# 07_DIGITAL_TRANSLATION.net
KiCad netlist of a schematic drawn in Altium Designer
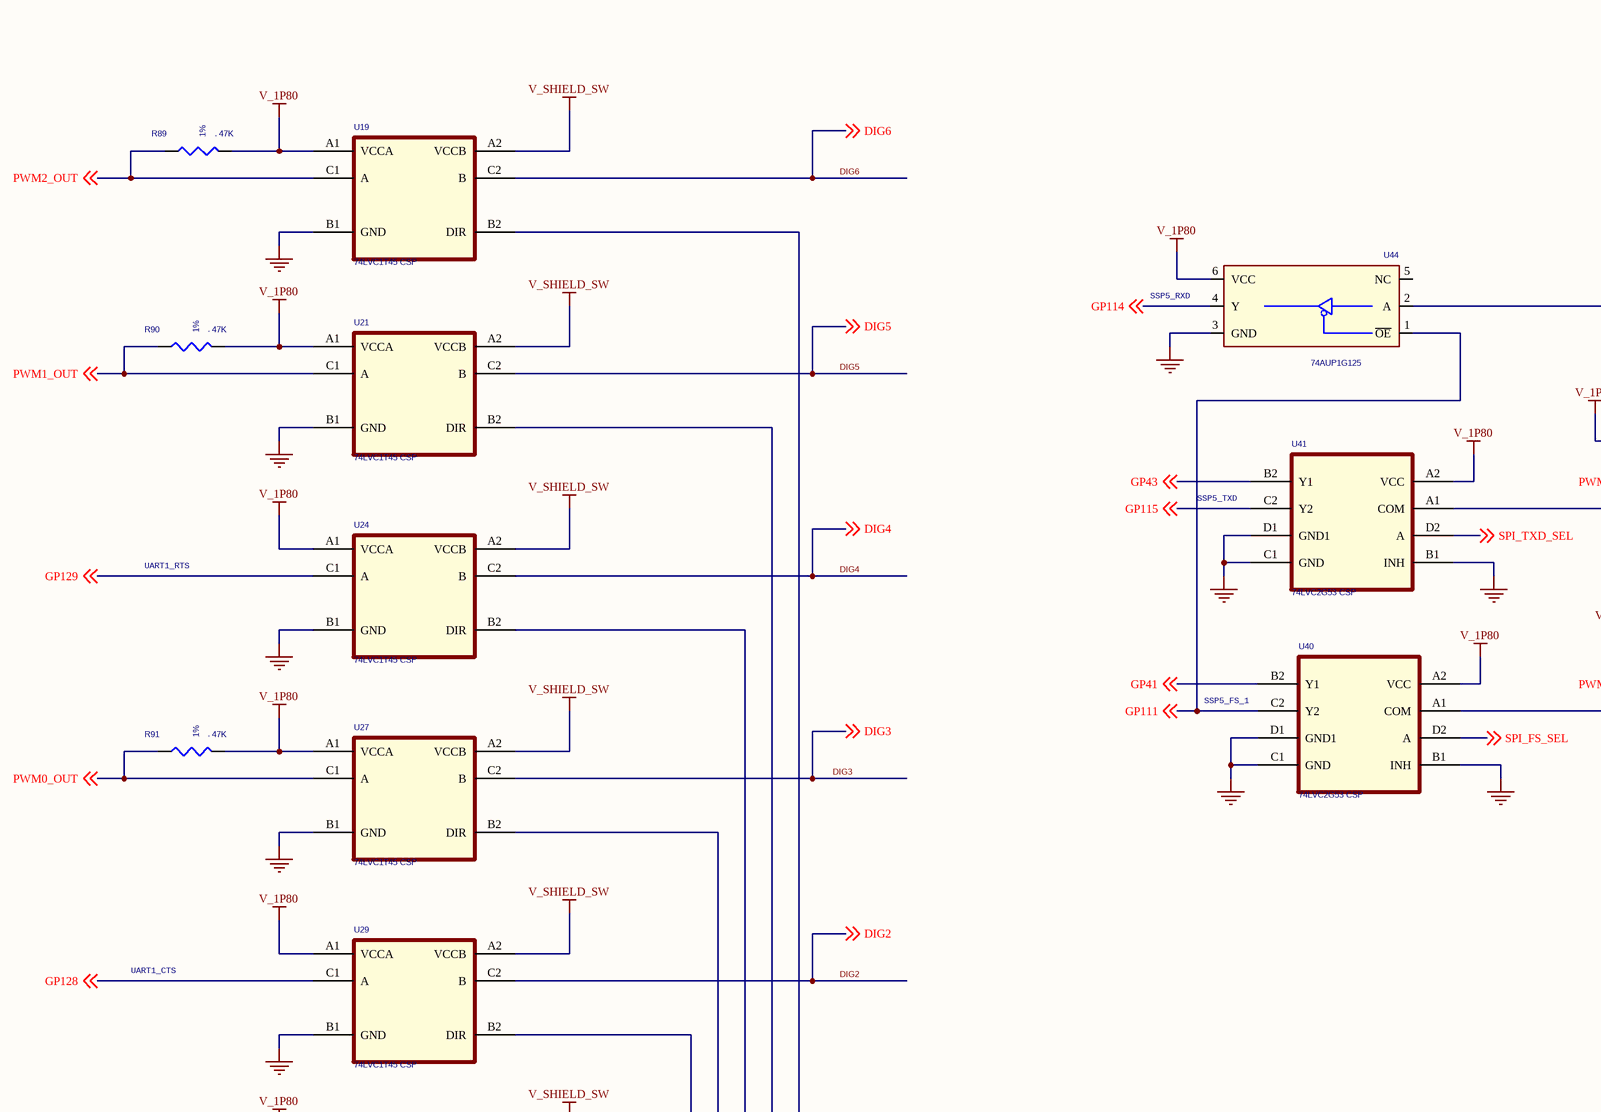
[diagram p0: 07) DIGITAL TRANSLATION.SchDoc, top left]
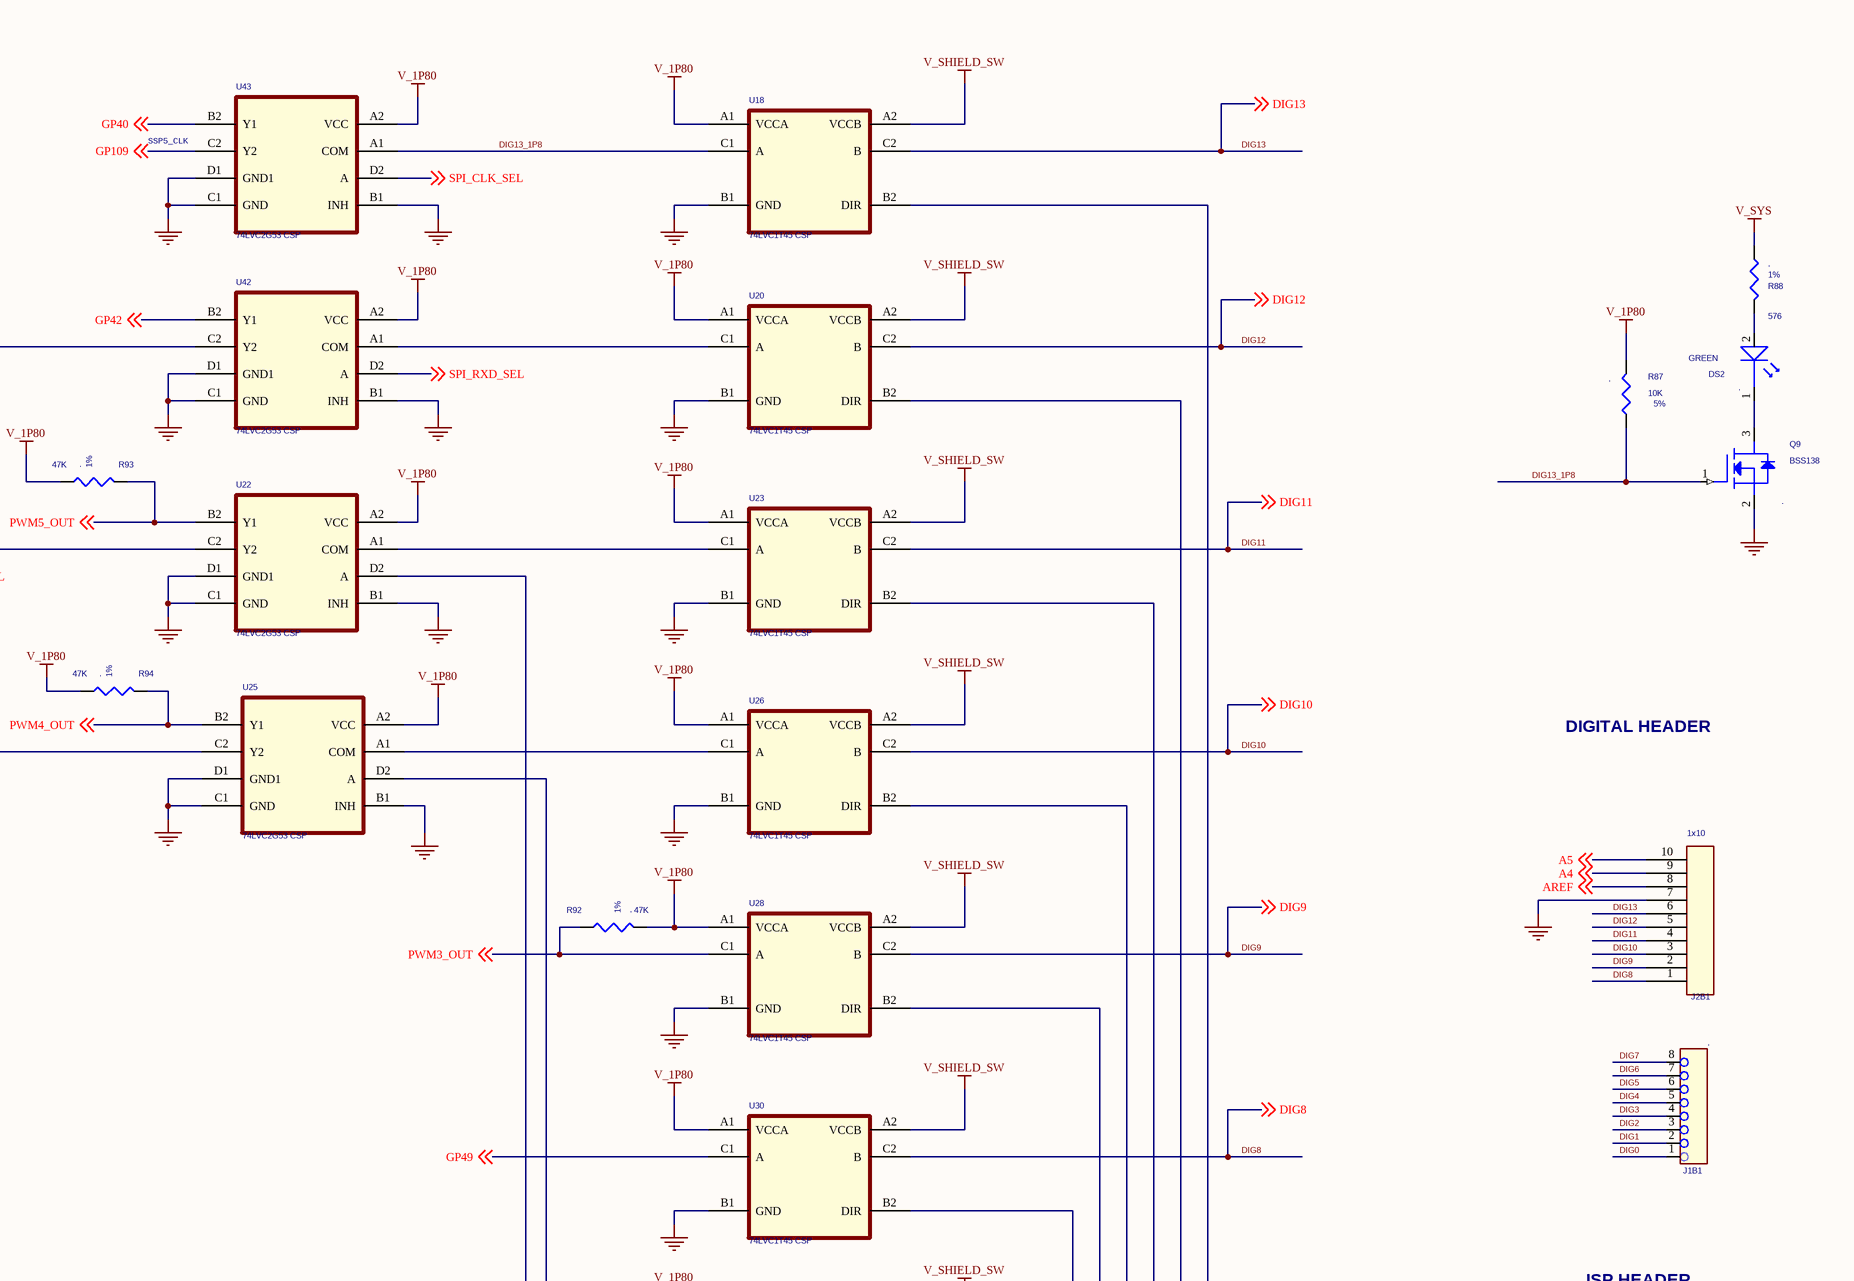
[diagram p1: 07) DIGITAL TRANSLATION.SchDoc, top right]
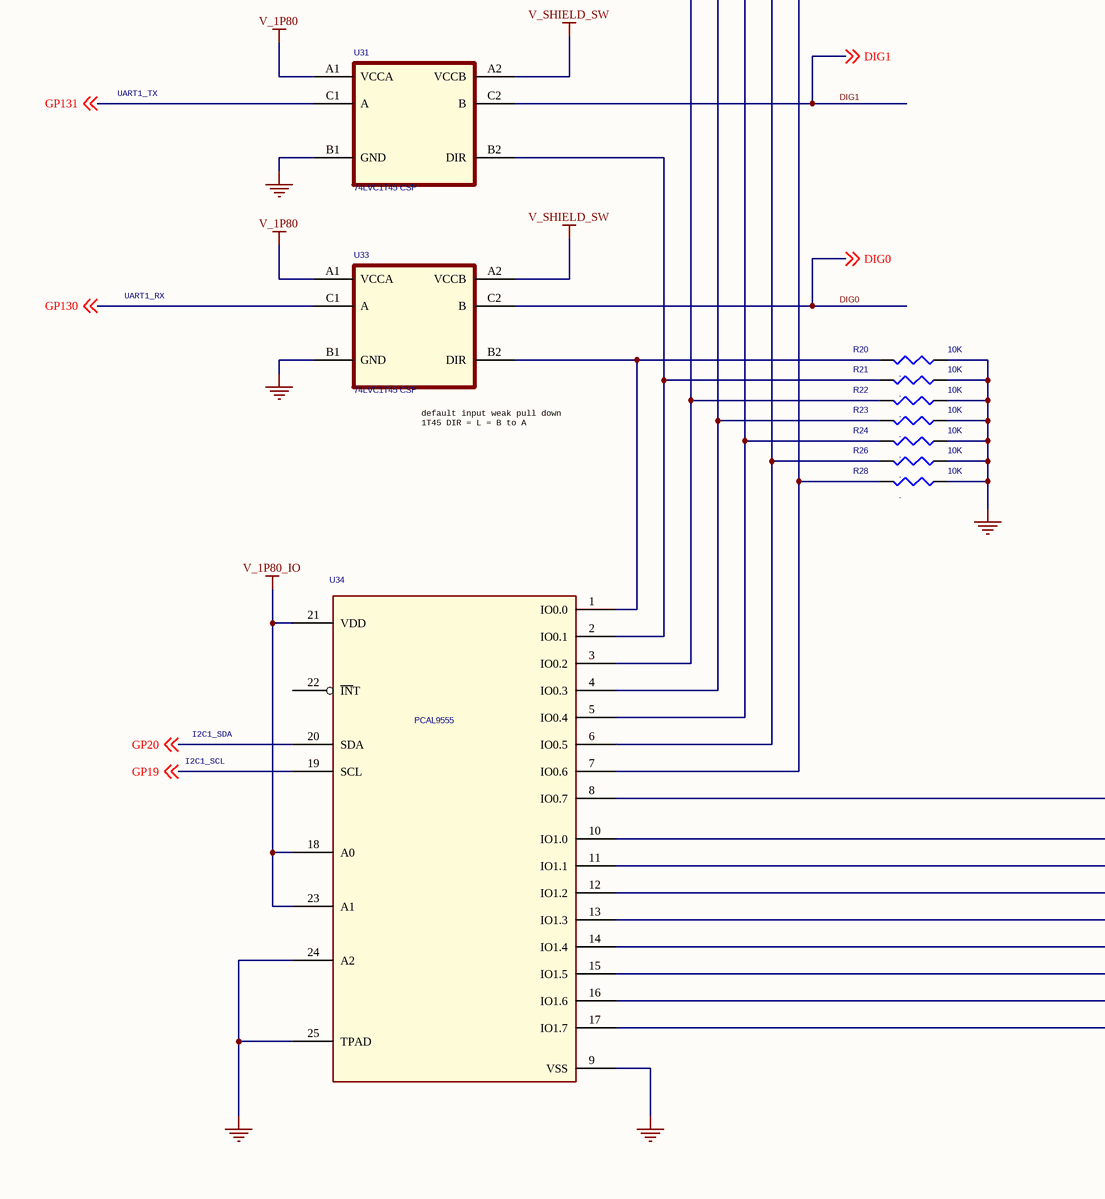
[diagram p2: 07) DIGITAL TRANSLATION.SchDoc, bottom left]
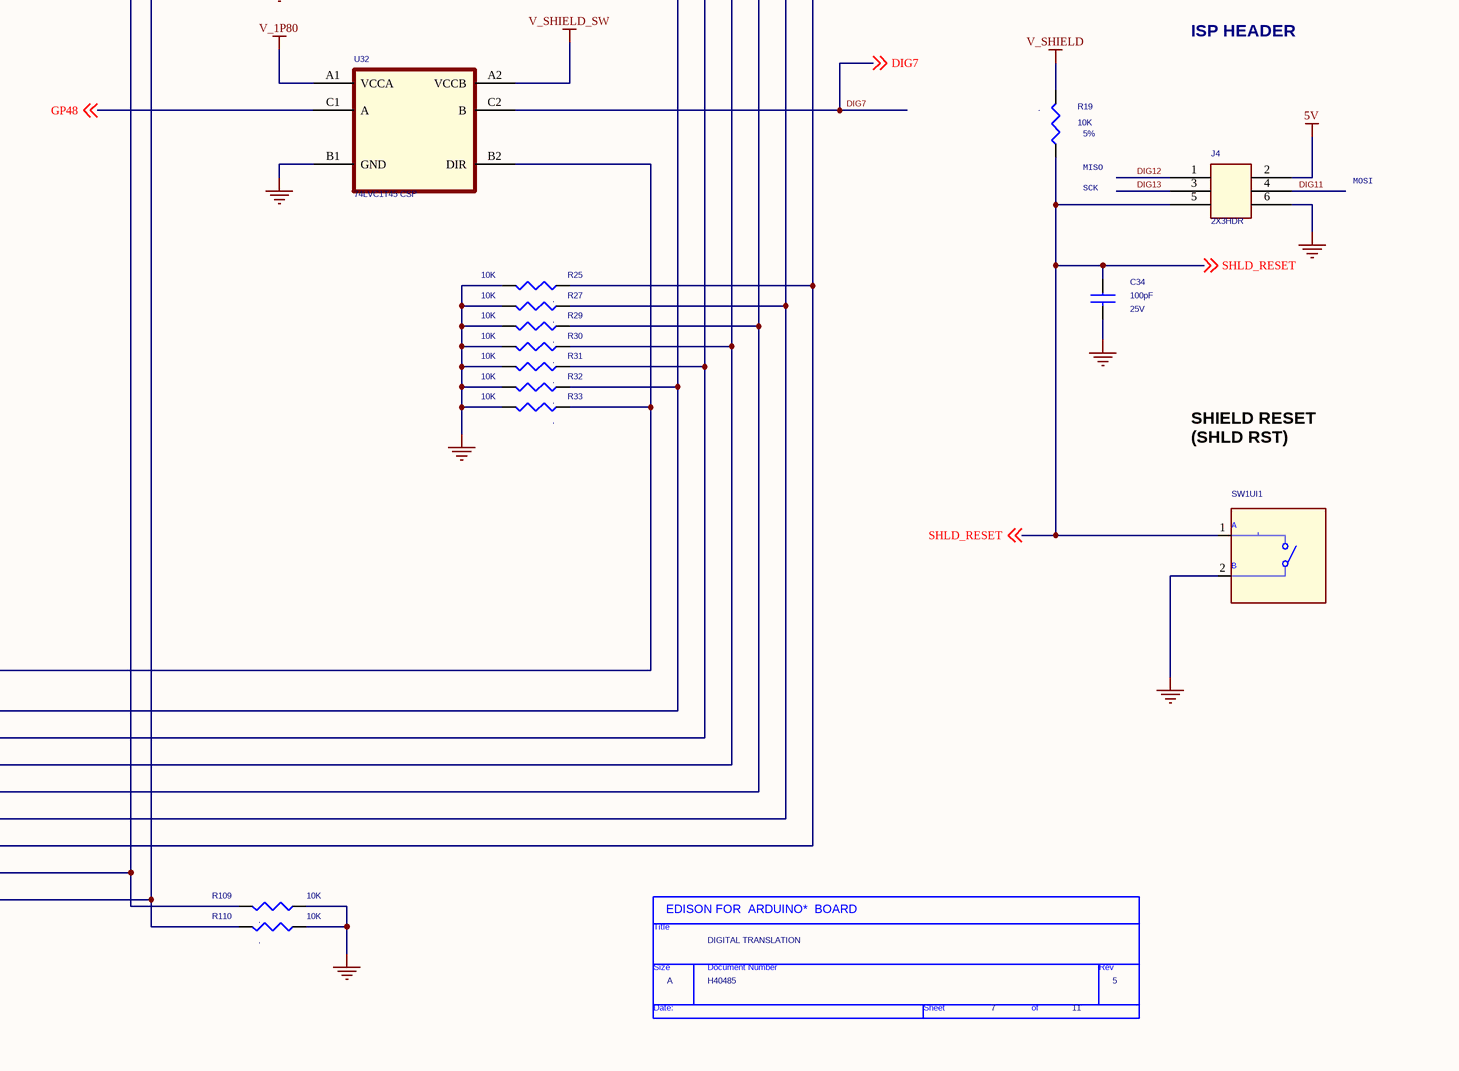
[diagram p3: 07) DIGITAL TRANSLATION.SchDoc, bottom right]

(export (version "E")
  (design (tool "Eeschema 10.0.6"))
  (components
    (comp (ref "C34")
      (value "100pF")
      (footprint "SMC0201")
      (description "CAPC,C0G,0201,100.000PF,25.000V,+/- 5%")
      (fields (field (name "PART_NUMBER") "D70542-001") (field (name "RATING") "25V"))
      (libsource (lib "*") (part "CAPC,COG,0201,25V,5%,100pF"))
    )
    (comp (ref "DS2")
      (value "GREEN")
      (footprint "smled0402")
      (description "LED,1005,SM,GRN,V,1.00,RC,1")
      (fields (field (name "NO_STUFF") ".") (field (name "PART_NUMBER") "E54986-003"))
      (libsource (lib "*") (part "LED,SMT,GREEN,V,0402"))
    )
    (comp (ref "J1B1")
      (value "CON8_HDR")
      (footprint "1x8hdr_p100in_th")
      (description "CONN,PLUG,VERT,1X8,2.54MM,THM,90147_1108")
      (fields (field (name "NO_STUFF") ".") (field (name "PART_NUMBER") "H46118-001"))
      (libsource (lib "*") (part "CON8,HDR,TH,0.1in,E70026-001"))
    )
    (comp (ref "J2B1")
      (value "1x10")
      (footprint "con10_1x10")
      (description "CONN,PLUG,VERT,1X10,2.54MM,THM,10CIRCUITS,90147_1110")
      (fields (field (name "PART_NUMBER") "H46116-001"))
      (libsource (lib "*") (part "CON10,1X10,0.1,0.093,E74918-001"))
    )
    (comp (ref "J4")
      (value "2X3HDR")
      (footprint "HDR_2X3DP")
      (description "CONN,HDR,2X3,PLG,VT,0.1,0.93 ST")
      (fields (field (name "PART_NUMBER") "H18587-001"))
      (libsource (lib "*") (part "CON6,HDR,TH,0_0.1,C77978-007"))
    )
    (comp (ref "Q9")
      (value "BSS138")
      (footprint "SOT23")
      (description "IC,DS,FET N,SOT-23,BSS138LT3G")
      (fields (field (name "NO_STUFF") ".") (field (name "PART_NUMBER") "C81974-001"))
      (libsource (lib "*") (part "XSTR,BSS138,FET,NCH,SOT23"))
    )
    (comp (ref "R19")
      (value "10K")
      (footprint "SMR0201")
      (description "RES D,0201,10.00 kOHM,5.00%,1/20W,YES")
      (fields
        (field (name "NO_STUFF") ".")
        (field (name "TOL") "5%")
        (field (name "PART_NUMBER") "C80792-002")
      )
      (libsource (lib "*") (part "RESD,0201,5%,1/20W,10K"))
    )
    (comp (ref "R20")
      (value "10K")
      (footprint "SMR0201")
      (description "RES D,0201,10.00 kOHM,5.00%,1/20W,YES")
      (fields (field (name "NO_STUFF") ".") (field (name "PART_NUMBER") "C80792-002"))
      (libsource (lib "*") (part "RESD,0201,5%,1/20W,10K"))
    )
    (comp (ref "R21")
      (value "10K")
      (footprint "SMR0201")
      (description "RES D,0201,10.00 kOHM,5.00%,1/20W,YES")
      (fields (field (name "NO_STUFF") ".") (field (name "PART_NUMBER") "C80792-002"))
      (libsource (lib "*") (part "RESD,0201,5%,1/20W,10K"))
    )
    (comp (ref "R22")
      (value "10K")
      (footprint "SMR0201")
      (description "RES D,0201,10.00 kOHM,5.00%,1/20W,YES")
      (fields (field (name "NO_STUFF") ".") (field (name "PART_NUMBER") "C80792-002"))
      (libsource (lib "*") (part "RESD,0201,5%,1/20W,10K"))
    )
    (comp (ref "R23")
      (value "10K")
      (footprint "SMR0201")
      (description "RES D,0201,10.00 kOHM,5.00%,1/20W,YES")
      (fields (field (name "NO_STUFF") ".") (field (name "PART_NUMBER") "C80792-002"))
      (libsource (lib "*") (part "RESD,0201,5%,1/20W,10K"))
    )
    (comp (ref "R24")
      (value "10K")
      (footprint "SMR0201")
      (description "RES D,0201,10.00 kOHM,5.00%,1/20W,YES")
      (fields (field (name "NO_STUFF") ".") (field (name "PART_NUMBER") "C80792-002"))
      (libsource (lib "*") (part "RESD,0201,5%,1/20W,10K"))
    )
    (comp (ref "R25")
      (value "10K")
      (footprint "SMR0201")
      (description "RES D,0201,10.00 kOHM,5.00%,1/20W,YES")
      (fields (field (name "NO_STUFF") ".") (field (name "PART_NUMBER") "C80792-002"))
      (libsource (lib "*") (part "RESD,0201,5%,1/20W,10K"))
    )
    (comp (ref "R26")
      (value "10K")
      (footprint "SMR0201")
      (description "RES D,0201,10.00 kOHM,5.00%,1/20W,YES")
      (fields (field (name "NO_STUFF") ".") (field (name "PART_NUMBER") "C80792-002"))
      (libsource (lib "*") (part "RESD,0201,5%,1/20W,10K"))
    )
    (comp (ref "R27")
      (value "10K")
      (footprint "SMR0201")
      (description "RES D,0201,10.00 kOHM,5.00%,1/20W,YES")
      (fields (field (name "NO_STUFF") ".") (field (name "PART_NUMBER") "C80792-002"))
      (libsource (lib "*") (part "RESD,0201,5%,1/20W,10K"))
    )
    (comp (ref "R28")
      (value "10K")
      (footprint "SMR0201")
      (description "RES D,0201,10.00 kOHM,5.00%,1/20W,YES")
      (fields (field (name "NO_STUFF") ".") (field (name "PART_NUMBER") "C80792-002"))
      (libsource (lib "*") (part "RESD,0201,5%,1/20W,10K"))
    )
    (comp (ref "R29")
      (value "10K")
      (footprint "SMR0201")
      (description "RES D,0201,10.00 kOHM,5.00%,1/20W,YES")
      (fields (field (name "NO_STUFF") ".") (field (name "PART_NUMBER") "C80792-002"))
      (libsource (lib "*") (part "RESD,0201,5%,1/20W,10K"))
    )
    (comp (ref "R30")
      (value "10K")
      (footprint "SMR0201")
      (description "RES D,0201,10.00 kOHM,5.00%,1/20W,YES")
      (fields (field (name "NO_STUFF") ".") (field (name "PART_NUMBER") "C80792-002"))
      (libsource (lib "*") (part "RESD,0201,5%,1/20W,10K"))
    )
    (comp (ref "R31")
      (value "10K")
      (footprint "SMR0201")
      (description "RES D,0201,10.00 kOHM,5.00%,1/20W,YES")
      (fields (field (name "NO_STUFF") ".") (field (name "PART_NUMBER") "C80792-002"))
      (libsource (lib "*") (part "RESD,0201,5%,1/20W,10K"))
    )
    (comp (ref "R32")
      (value "10K")
      (footprint "SMR0201")
      (description "RES D,0201,10.00 kOHM,5.00%,1/20W,YES")
      (fields (field (name "NO_STUFF") ".") (field (name "PART_NUMBER") "C80792-002"))
      (libsource (lib "*") (part "RESD,0201,5%,1/20W,10K"))
    )
    (comp (ref "R33")
      (value "10K")
      (footprint "SMR0201")
      (description "RES D,0201,10.00 kOHM,5.00%,1/20W,YES")
      (fields (field (name "NO_STUFF") ".") (field (name "PART_NUMBER") "C80792-002"))
      (libsource (lib "*") (part "RESD,0201,5%,1/20W,10K"))
    )
    (comp (ref "R87")
      (value "10K")
      (footprint "SMR0201")
      (description "RES D,0201,10.00 kOHM,5.00%,1/20W,YES")
      (fields
        (field (name "NO_STUFF") ".")
        (field (name "TOL") "5%")
        (field (name "PART_NUMBER") "C80792-002")
      )
      (libsource (lib "*") (part "RESD,0201,5%,1/20W,10K"))
    )
    (comp (ref "R88")
      (value "576")
      (footprint "SMR0201")
      (description "RES D,0402,576.00 OHM,1.00%,1/16W,YES")
      (fields
        (field (name "NO_STUFF") ".")
        (field (name "TOL") "1%")
        (field (name "PART_NUMBER") "A93548-403")
      )
      (libsource (lib "*") (part "RESD,0201,1%,1/20W,562"))
    )
    (comp (ref "R89")
      (value "47K")
      (footprint "SMR0201")
      (description "RES_D,0201,47.0kOHM,1.00%,1/20W,")
      (fields
        (field (name "PART_NUMBER") "C48657-118")
        (field (name "TOL") "1%")
        (field (name "NO_STUFF") ".")
      )
      (libsource (lib "*") (part "RESD,0201,1%,1/20W,47K"))
    )
    (comp (ref "R90")
      (value "47K")
      (footprint "SMR0201")
      (description "RES_D,0201,47.0kOHM,1.00%,1/20W,")
      (fields
        (field (name "PART_NUMBER") "C48657-118")
        (field (name "TOL") "1%")
        (field (name "NO_STUFF") ".")
      )
      (libsource (lib "*") (part "RESD,0201,1%,1/20W,47K"))
    )
    (comp (ref "R91")
      (value "47K")
      (footprint "SMR0201")
      (description "RES_D,0201,47.0kOHM,1.00%,1/20W,")
      (fields
        (field (name "PART_NUMBER") "C48657-118")
        (field (name "TOL") "1%")
        (field (name "NO_STUFF") ".")
      )
      (libsource (lib "*") (part "RESD,0201,1%,1/20W,47K"))
    )
    (comp (ref "R92")
      (value "47K")
      (footprint "SMR0201")
      (description "RES_D,0201,47.0kOHM,1.00%,1/20W,")
      (fields
        (field (name "PART_NUMBER") "C48657-118")
        (field (name "TOL") "1%")
        (field (name "NO_STUFF") ".")
      )
      (libsource (lib "*") (part "RESD,0201,1%,1/20W,47K"))
    )
    (comp (ref "R93")
      (value "47K")
      (footprint "SMR0201")
      (description "RES_D,0201,47.0kOHM,1.00%,1/20W,")
      (fields
        (field (name "PART_NUMBER") "C48657-118")
        (field (name "TOL") "1%")
        (field (name "NO_STUFF") ".")
      )
      (libsource (lib "*") (part "RESD,0201,1%,1/20W,47K"))
    )
    (comp (ref "R94")
      (value "47K")
      (footprint "SMR0201")
      (description "RES_D,0201,47.0kOHM,1.00%,1/20W,")
      (fields
        (field (name "PART_NUMBER") "C48657-118")
        (field (name "TOL") "1%")
        (field (name "NO_STUFF") ".")
      )
      (libsource (lib "*") (part "RESD,0201,1%,1/20W,47K"))
    )
    (comp (ref "R109")
      (value "10K")
      (footprint "SMR0201")
      (description "RES D,0201,10.00 kOHM,5.00%,1/20W,YES")
      (fields (field (name "NO_STUFF") ".") (field (name "PART_NUMBER") "C80792-002"))
      (libsource (lib "*") (part "RESD,0201,5%,1/20W,10K"))
    )
    (comp (ref "R110")
      (value "10K")
      (footprint "SMR0201")
      (description "RES D,0201,10.00 kOHM,5.00%,1/20W,YES")
      (fields (field (name "NO_STUFF") ".") (field (name "PART_NUMBER") "C80792-002"))
      (libsource (lib "*") (part "RESD,0201,5%,1/20W,10K"))
    )
    (comp (ref "SW1UI1")
      (value "LIGHT TOUCH SWITCH EVQP7J01P")
      (footprint "sw_evqp7_4p")
      (description "CONN,SWIT,TACTILE,VT,SPST,2,50.0 mA,SMT>")
      (fields (field (name "MFG") "Panasonic") (field (name "PART_NUMBER") "D90553-001"))
      (libsource (lib "*") (part "SWITCH,EVQP7J01P,4P,PWR_0"))
    )
    (comp (ref "U18")
      (value "74LVC1T45 CSP")
      (footprint "bga6_5mm_37x57")
      (description "IC,LOG,TRANSCEIVE,CSP,SN74LVC1T45,NI3S,")
      (fields (field (name "PART_NUMBER") "G42189-001") (field (name "MFG") "TI"))
      (libsource (lib "*") (part "IC,74LVC1T45,LOG,BGA6,TRNSSVR"))
    )
    (comp (ref "U19")
      (value "74LVC1T45 CSP")
      (footprint "bga6_5mm_37x57")
      (description "IC,LOG,TRANSCEIVE,CSP,SN74LVC1T45,NI3S,")
      (fields (field (name "PART_NUMBER") "G42189-001") (field (name "MFG") "TI"))
      (libsource (lib "*") (part "IC,74LVC1T45,LOG,BGA6,TRNSSVR"))
    )
    (comp (ref "U20")
      (value "74LVC1T45 CSP")
      (footprint "bga6_5mm_37x57")
      (description "IC,LOG,TRANSCEIVE,CSP,SN74LVC1T45,NI3S,")
      (fields (field (name "PART_NUMBER") "G42189-001") (field (name "MFG") "TI"))
      (libsource (lib "*") (part "IC,74LVC1T45,LOG,BGA6,TRNSSVR"))
    )
    (comp (ref "U21")
      (value "74LVC1T45 CSP")
      (footprint "bga6_5mm_37x57")
      (description "IC,LOG,TRANSCEIVE,CSP,SN74LVC1T45,NI3S,")
      (fields (field (name "PART_NUMBER") "G42189-001") (field (name "MFG") "TI"))
      (libsource (lib "*") (part "IC,74LVC1T45,LOG,BGA6,TRNSSVR"))
    )
    (comp (ref "U22")
      (value "74LVC2G53 CSP")
      (footprint "bga8_2X4_P5MM")
      (description "IC,LOG,MULTIPLEX,uBGA,742G53,NI,")
      (fields (field (name "PART_NUMBER") "H40914-001") (field (name "MFG") "TI"))
      (libsource (lib "*") (part "IC,74LVC2G53"))
    )
    (comp (ref "U23")
      (value "74LVC1T45 CSP")
      (footprint "bga6_5mm_37x57")
      (description "IC,LOG,TRANSCEIVE,CSP,SN74LVC1T45,NI3S,")
      (fields (field (name "PART_NUMBER") "G42189-001") (field (name "MFG") "TI"))
      (libsource (lib "*") (part "IC,74LVC1T45,LOG,BGA6,TRNSSVR"))
    )
    (comp (ref "U24")
      (value "74LVC1T45 CSP")
      (footprint "bga6_5mm_37x57")
      (description "IC,LOG,TRANSCEIVE,CSP,SN74LVC1T45,NI3S,")
      (fields (field (name "PART_NUMBER") "G42189-001") (field (name "MFG") "TI"))
      (libsource (lib "*") (part "IC,74LVC1T45,LOG,BGA6,TRNSSVR"))
    )
    (comp (ref "U25")
      (value "74LVC2G53 CSP")
      (footprint "bga8_2X4_P5MM")
      (description "IC,LOG,MULTIPLEX,uBGA,742G53,NI,")
      (fields (field (name "PART_NUMBER") "H40914-001") (field (name "MFG") "TI"))
      (libsource (lib "*") (part "IC,74LVC2G53"))
    )
    (comp (ref "U26")
      (value "74LVC1T45 CSP")
      (footprint "bga6_5mm_37x57")
      (description "IC,LOG,TRANSCEIVE,CSP,SN74LVC1T45,NI3S,")
      (fields (field (name "PART_NUMBER") "G42189-001") (field (name "MFG") "TI"))
      (libsource (lib "*") (part "IC,74LVC1T45,LOG,BGA6,TRNSSVR"))
    )
    (comp (ref "U27")
      (value "74LVC1T45 CSP")
      (footprint "bga6_5mm_37x57")
      (description "IC,LOG,TRANSCEIVE,CSP,SN74LVC1T45,NI3S,")
      (fields (field (name "PART_NUMBER") "G42189-001") (field (name "MFG") "TI"))
      (libsource (lib "*") (part "IC,74LVC1T45,LOG,BGA6,TRNSSVR"))
    )
    (comp (ref "U28")
      (value "74LVC1T45 CSP")
      (footprint "bga6_5mm_37x57")
      (description "IC,LOG,TRANSCEIVE,CSP,SN74LVC1T45,NI3S,")
      (fields (field (name "PART_NUMBER") "G42189-001") (field (name "MFG") "TI"))
      (libsource (lib "*") (part "IC,74LVC1T45,LOG,BGA6,TRNSSVR"))
    )
    (comp (ref "U29")
      (value "74LVC1T45 CSP")
      (footprint "bga6_5mm_37x57")
      (description "IC,LOG,TRANSCEIVE,CSP,SN74LVC1T45,NI3S,")
      (fields (field (name "PART_NUMBER") "G42189-001") (field (name "MFG") "TI"))
      (libsource (lib "*") (part "IC,74LVC1T45,LOG,BGA6,TRNSSVR"))
    )
    (comp (ref "U30")
      (value "74LVC1T45 CSP")
      (footprint "bga6_5mm_37x57")
      (description "IC,LOG,TRANSCEIVE,CSP,SN74LVC1T45,NI3S,")
      (fields (field (name "PART_NUMBER") "G42189-001") (field (name "MFG") "TI"))
      (libsource (lib "*") (part "IC,74LVC1T45,LOG,BGA6,TRNSSVR"))
    )
    (comp (ref "U31")
      (value "74LVC1T45 CSP")
      (footprint "bga6_5mm_37x57")
      (description "IC,LOG,TRANSCEIVE,CSP,SN74LVC1T45,NI3S,")
      (fields (field (name "PART_NUMBER") "G42189-001") (field (name "MFG") "TI"))
      (libsource (lib "*") (part "IC,74LVC1T45,LOG,BGA6,TRNSSVR"))
    )
    (comp (ref "U32")
      (value "74LVC1T45 CSP")
      (footprint "bga6_5mm_37x57")
      (description "IC,LOG,TRANSCEIVE,CSP,SN74LVC1T45,NI3S,")
      (fields (field (name "PART_NUMBER") "G42189-001") (field (name "MFG") "TI"))
      (libsource (lib "*") (part "IC,74LVC1T45,LOG,BGA6,TRNSSVR"))
    )
    (comp (ref "U33")
      (value "74LVC1T45 CSP")
      (footprint "bga6_5mm_37x57")
      (description "IC,LOG,TRANSCEIVE,CSP,SN74LVC1T45,NI3S,")
      (fields (field (name "PART_NUMBER") "G42189-001") (field (name "MFG") "TI"))
      (libsource (lib "*") (part "IC,74LVC1T45,LOG,BGA6,TRNSSVR"))
    )
    (comp (ref "U34")
      (value "PCAL9555")
      (footprint "LCC25_S41_5DF89X89MA")
      (description "IC,LIN,INTFC,QFN,PCAL9555,GPIO,")
      (fields (field (name "PART_NUMBER") "H31921-001"))
      (libsource (lib "*") (part "IC,PCAL9555,16bit_GPIO"))
    )
    (comp (ref "U40")
      (value "74LVC2G53 CSP")
      (footprint "bga8_2X4_P5MM")
      (description "IC,LOG,MULTIPLEX,uBGA,742G53,NI,")
      (fields (field (name "PART_NUMBER") "H40914-001") (field (name "MFG") "TI"))
      (libsource (lib "*") (part "IC,74LVC2G53"))
    )
    (comp (ref "U41")
      (value "74LVC2G53 CSP")
      (footprint "bga8_2X4_P5MM")
      (description "IC,LOG,MULTIPLEX,uBGA,742G53,NI,")
      (fields (field (name "PART_NUMBER") "H40914-001") (field (name "MFG") "TI"))
      (libsource (lib "*") (part "IC,74LVC2G53"))
    )
    (comp (ref "U42")
      (value "74LVC2G53 CSP")
      (footprint "bga8_2X4_P5MM")
      (description "IC,LOG,MULTIPLEX,uBGA,742G53,NI,")
      (fields (field (name "PART_NUMBER") "H40914-001") (field (name "MFG") "TI"))
      (libsource (lib "*") (part "IC,74LVC2G53"))
    )
    (comp (ref "U43")
      (value "74LVC2G53 CSP")
      (footprint "bga8_2X4_P5MM")
      (description "IC,LOG,MULTIPLEX,uBGA,742G53,NI,")
      (fields (field (name "PART_NUMBER") "H40914-001") (field (name "MFG") "TI"))
      (libsource (lib "*") (part "IC,74LVC2G53"))
    )
    (comp (ref "U44")
      (value "74AUP1G125")
      (footprint "LCC6_P35MM_SQ1P0_NONC_P5H")
      (description "IC,LOG,TRANSCEIVE,DFN,74AUP1G125,NI3S,")
      (fields (field (name "MFG") "TI") (field (name "PART_NUMBER") "H22984-001"))
      (libsource (lib "*") (part "IC,74AUP1G125,LOG,LCC6,BUFFER"))
    )
  )
  (nets
    (net (code "1") (name "/DIG13_1P8") (class "Default")
      (node (ref "Q9") (pin "1") (pinfunction "G_1") (pintype "input"))
      (node (ref "R87") (pin "1") (pinfunction "1_1") (pintype "passive"))
      (node (ref "U18") (pin "C1") (pinfunction "A_C1") (pintype "passive"))
      (node (ref "U43") (pin "A1") (pinfunction "COM_A1") (pintype "passive"))
    )
    (net (code "2") (name "5V") (class "Default")
      (node (ref "J4") (pin "2") (pinfunction "IO_2_2") (pintype "passive"))
    )
    (net (code "3") (name "A4") (class "Default")
      (node (ref "J2B1") (pin "9") (pinfunction "9_9") (pintype "passive"))
    )
    (net (code "4") (name "A5") (class "Default")
      (node (ref "J2B1") (pin "10") (pinfunction "10_10") (pintype "passive"))
    )
    (net (code "5") (name "AREF") (class "Default")
      (node (ref "J2B1") (pin "8") (pinfunction "8_8") (pintype "passive"))
    )
    (net (code "6") (name "DIG0") (class "Default")
      (node (ref "J1B1") (pin "1") (pinfunction "1_1") (pintype "passive"))
      (node (ref "U33") (pin "C2") (pinfunction "B_C2") (pintype "passive"))
    )
    (net (code "7") (name "DIG1") (class "Default")
      (node (ref "J1B1") (pin "2") (pinfunction "2_2") (pintype "passive"))
      (node (ref "U31") (pin "C2") (pinfunction "B_C2") (pintype "passive"))
    )
    (net (code "8") (name "DIG2") (class "Default")
      (node (ref "J1B1") (pin "3") (pinfunction "3_3") (pintype "passive"))
      (node (ref "U29") (pin "C2") (pinfunction "B_C2") (pintype "passive"))
    )
    (net (code "9") (name "DIG3") (class "Default")
      (node (ref "J1B1") (pin "4") (pinfunction "4_4") (pintype "passive"))
      (node (ref "U27") (pin "C2") (pinfunction "B_C2") (pintype "passive"))
    )
    (net (code "10") (name "DIG4") (class "Default")
      (node (ref "J1B1") (pin "5") (pinfunction "5_5") (pintype "passive"))
      (node (ref "U24") (pin "C2") (pinfunction "B_C2") (pintype "passive"))
    )
    (net (code "11") (name "DIG5") (class "Default")
      (node (ref "J1B1") (pin "6") (pinfunction "6_6") (pintype "passive"))
      (node (ref "U21") (pin "C2") (pinfunction "B_C2") (pintype "passive"))
    )
    (net (code "12") (name "DIG6") (class "Default")
      (node (ref "J1B1") (pin "7") (pinfunction "7_7") (pintype "passive"))
      (node (ref "U19") (pin "C2") (pinfunction "B_C2") (pintype "passive"))
    )
    (net (code "13") (name "DIG7") (class "Default")
      (node (ref "J1B1") (pin "8") (pinfunction "8_8") (pintype "passive"))
      (node (ref "U32") (pin "C2") (pinfunction "B_C2") (pintype "passive"))
    )
    (net (code "14") (name "DIG8") (class "Default")
      (node (ref "J2B1") (pin "1") (pinfunction "1_1") (pintype "passive"))
      (node (ref "U30") (pin "C2") (pinfunction "B_C2") (pintype "passive"))
    )
    (net (code "15") (name "DIG9") (class "Default")
      (node (ref "J2B1") (pin "2") (pinfunction "2_2") (pintype "passive"))
      (node (ref "U28") (pin "C2") (pinfunction "B_C2") (pintype "passive"))
    )
    (net (code "16") (name "DIG10") (class "Default")
      (node (ref "J2B1") (pin "3") (pinfunction "3_3") (pintype "passive"))
      (node (ref "U26") (pin "C2") (pinfunction "B_C2") (pintype "passive"))
    )
    (net (code "17") (name "DIG11") (class "Default")
      (node (ref "J2B1") (pin "4") (pinfunction "4_4") (pintype "passive"))
      (node (ref "J4") (pin "4") (pinfunction "IO_4_4") (pintype "passive"))
      (node (ref "U23") (pin "C2") (pinfunction "B_C2") (pintype "passive"))
    )
    (net (code "18") (name "DIG12") (class "Default")
      (node (ref "J2B1") (pin "5") (pinfunction "5_5") (pintype "passive"))
      (node (ref "J4") (pin "1") (pinfunction "IO_1_1") (pintype "passive"))
      (node (ref "U20") (pin "C2") (pinfunction "B_C2") (pintype "passive"))
    )
    (net (code "19") (name "DIG13") (class "Default")
      (node (ref "J2B1") (pin "6") (pinfunction "6_6") (pintype "passive"))
      (node (ref "J4") (pin "3") (pinfunction "IO_3_3") (pintype "passive"))
      (node (ref "U18") (pin "C2") (pinfunction "B_C2") (pintype "passive"))
    )
    (net (code "20") (name "GND") (class "Default")
      (node (ref "C34") (pin "2") (pinfunction "2_2") (pintype "passive"))
      (node (ref "J2B1") (pin "7") (pinfunction "7_7") (pintype "passive"))
      (node (ref "J4") (pin "6") (pinfunction "IO_6_6") (pintype "passive"))
      (node (ref "Q9") (pin "2") (pinfunction "S_2") (pintype "passive"))
      (node (ref "R109") (pin "1") (pinfunction "1_1") (pintype "passive"))
      (node (ref "R110") (pin "1") (pinfunction "1_1") (pintype "passive"))
      (node (ref "R20") (pin "1") (pinfunction "1_1") (pintype "passive"))
      (node (ref "R21") (pin "1") (pinfunction "1_1") (pintype "passive"))
      (node (ref "R22") (pin "1") (pinfunction "1_1") (pintype "passive"))
      (node (ref "R23") (pin "1") (pinfunction "1_1") (pintype "passive"))
      (node (ref "R24") (pin "1") (pinfunction "1_1") (pintype "passive"))
      (node (ref "R25") (pin "1") (pinfunction "1_1") (pintype "passive"))
      (node (ref "R26") (pin "1") (pinfunction "1_1") (pintype "passive"))
      (node (ref "R27") (pin "1") (pinfunction "1_1") (pintype "passive"))
      (node (ref "R28") (pin "1") (pinfunction "1_1") (pintype "passive"))
      (node (ref "R29") (pin "1") (pinfunction "1_1") (pintype "passive"))
      (node (ref "R30") (pin "1") (pinfunction "1_1") (pintype "passive"))
      (node (ref "R31") (pin "1") (pinfunction "1_1") (pintype "passive"))
      (node (ref "R32") (pin "1") (pinfunction "1_1") (pintype "passive"))
      (node (ref "R33") (pin "1") (pinfunction "1_1") (pintype "passive"))
      (node (ref "SW1UI1") (pin "2") (pinfunction "B_2") (pintype "bidirectional"))
      (node (ref "U18") (pin "B1") (pinfunction "GND_B1") (pintype "passive"))
      (node (ref "U19") (pin "B1") (pinfunction "GND_B1") (pintype "passive"))
      (node (ref "U20") (pin "B1") (pinfunction "GND_B1") (pintype "passive"))
      (node (ref "U21") (pin "B1") (pinfunction "GND_B1") (pintype "passive"))
      (node (ref "U22") (pin "B1") (pinfunction "INH_B1") (pintype "passive"))
      (node (ref "U22") (pin "C1") (pinfunction "GND_C1") (pintype "passive"))
      (node (ref "U22") (pin "D1") (pinfunction "GND1_D1") (pintype "passive"))
      (node (ref "U23") (pin "B1") (pinfunction "GND_B1") (pintype "passive"))
      (node (ref "U24") (pin "B1") (pinfunction "GND_B1") (pintype "passive"))
      (node (ref "U25") (pin "B1") (pinfunction "INH_B1") (pintype "passive"))
      (node (ref "U25") (pin "C1") (pinfunction "GND_C1") (pintype "passive"))
      (node (ref "U25") (pin "D1") (pinfunction "GND1_D1") (pintype "passive"))
      (node (ref "U26") (pin "B1") (pinfunction "GND_B1") (pintype "passive"))
      (node (ref "U27") (pin "B1") (pinfunction "GND_B1") (pintype "passive"))
      (node (ref "U28") (pin "B1") (pinfunction "GND_B1") (pintype "passive"))
      (node (ref "U29") (pin "B1") (pinfunction "GND_B1") (pintype "passive"))
      (node (ref "U30") (pin "B1") (pinfunction "GND_B1") (pintype "passive"))
      (node (ref "U31") (pin "B1") (pinfunction "GND_B1") (pintype "passive"))
      (node (ref "U32") (pin "B1") (pinfunction "GND_B1") (pintype "passive"))
      (node (ref "U33") (pin "B1") (pinfunction "GND_B1") (pintype "passive"))
      (node (ref "U34") (pin "24") (pinfunction "A2_24") (pintype "passive"))
      (node (ref "U34") (pin "25") (pinfunction "TPAD_25") (pintype "passive"))
      (node (ref "U34") (pin "9") (pinfunction "VSS_9") (pintype "passive"))
      (node (ref "U40") (pin "B1") (pinfunction "INH_B1") (pintype "passive"))
      (node (ref "U40") (pin "C1") (pinfunction "GND_C1") (pintype "passive"))
      (node (ref "U40") (pin "D1") (pinfunction "GND1_D1") (pintype "passive"))
      (node (ref "U41") (pin "B1") (pinfunction "INH_B1") (pintype "passive"))
      (node (ref "U41") (pin "C1") (pinfunction "GND_C1") (pintype "passive"))
      (node (ref "U41") (pin "D1") (pinfunction "GND1_D1") (pintype "passive"))
      (node (ref "U42") (pin "B1") (pinfunction "INH_B1") (pintype "passive"))
      (node (ref "U42") (pin "C1") (pinfunction "GND_C1") (pintype "passive"))
      (node (ref "U42") (pin "D1") (pinfunction "GND1_D1") (pintype "passive"))
      (node (ref "U43") (pin "B1") (pinfunction "INH_B1") (pintype "passive"))
      (node (ref "U43") (pin "C1") (pinfunction "GND_C1") (pintype "passive"))
      (node (ref "U43") (pin "D1") (pinfunction "GND1_D1") (pintype "passive"))
      (node (ref "U44") (pin "3") (pinfunction "GND_3") (pintype "passive"))
    )
    (net (code "21") (name "GP19") (class "Default")
      (node (ref "U34") (pin "19") (pinfunction "SCL_19") (pintype "passive"))
    )
    (net (code "22") (name "GP20") (class "Default")
      (node (ref "U34") (pin "20") (pinfunction "SDA_20") (pintype "passive"))
    )
    (net (code "23") (name "GP40") (class "Default")
      (node (ref "U43") (pin "B2") (pinfunction "Y1_B2") (pintype "passive"))
    )
    (net (code "24") (name "GP41") (class "Default")
      (node (ref "U40") (pin "B2") (pinfunction "Y1_B2") (pintype "passive"))
    )
    (net (code "25") (name "GP42") (class "Default")
      (node (ref "U42") (pin "B2") (pinfunction "Y1_B2") (pintype "passive"))
    )
    (net (code "26") (name "GP43") (class "Default")
      (node (ref "U41") (pin "B2") (pinfunction "Y1_B2") (pintype "passive"))
    )
    (net (code "27") (name "GP48") (class "Default")
      (node (ref "U32") (pin "C1") (pinfunction "A_C1") (pintype "passive"))
    )
    (net (code "28") (name "GP49") (class "Default")
      (node (ref "U30") (pin "C1") (pinfunction "A_C1") (pintype "passive"))
    )
    (net (code "29") (name "GP109") (class "Default")
      (node (ref "U43") (pin "C2") (pinfunction "Y2_C2") (pintype "passive"))
    )
    (net (code "30") (name "GP111") (class "Default")
      (node (ref "U40") (pin "C2") (pinfunction "Y2_C2") (pintype "passive"))
      (node (ref "U44") (pin "1") (pinfunction "~{OE}_1") (pintype "passive"))
    )
    (net (code "31") (name "GP114") (class "Default")
      (node (ref "U44") (pin "4") (pinfunction "Y_4") (pintype "passive"))
    )
    (net (code "32") (name "GP115") (class "Default")
      (node (ref "U41") (pin "C2") (pinfunction "Y2_C2") (pintype "passive"))
    )
    (net (code "33") (name "GP128") (class "Default")
      (node (ref "U29") (pin "C1") (pinfunction "A_C1") (pintype "passive"))
    )
    (net (code "34") (name "GP129") (class "Default")
      (node (ref "U24") (pin "C1") (pinfunction "A_C1") (pintype "passive"))
    )
    (net (code "35") (name "GP130") (class "Default")
      (node (ref "U33") (pin "C1") (pinfunction "A_C1") (pintype "passive"))
    )
    (net (code "36") (name "GP131") (class "Default")
      (node (ref "U31") (pin "C1") (pinfunction "A_C1") (pintype "passive"))
    )
    (net (code "37") (name "Net-(DS2-LED1)") (class "Default")
      (node (ref "DS2") (pin "1") (pinfunction "LED1_1") (pintype "passive"))
      (node (ref "Q9") (pin "3") (pinfunction "D_3") (pintype "passive"))
    )
    (net (code "38") (name "Net-(DS2-LED2)") (class "Default")
      (node (ref "DS2") (pin "2") (pinfunction "LED2_2") (pintype "passive"))
      (node (ref "R88") (pin "1") (pinfunction "1_1") (pintype "passive"))
    )
    (net (code "39") (name "Net-(U18-DIR)") (class "Default")
      (node (ref "R25") (pin "2") (pinfunction "2_2") (pintype "passive"))
      (node (ref "U18") (pin "B2") (pinfunction "DIR_B2") (pintype "passive"))
      (node (ref "U34") (pin "15") (pinfunction "IO1.5_15") (pintype "passive"))
    )
    (net (code "40") (name "Net-(U19-DIR)") (class "Default")
      (node (ref "R28") (pin "2") (pinfunction "2_2") (pintype "passive"))
      (node (ref "U19") (pin "B2") (pinfunction "DIR_B2") (pintype "passive"))
      (node (ref "U34") (pin "7") (pinfunction "IO0.6_7") (pintype "passive"))
    )
    (net (code "41") (name "Net-(U20-A)") (class "Default")
      (node (ref "U20") (pin "C1") (pinfunction "A_C1") (pintype "passive"))
      (node (ref "U42") (pin "A1") (pinfunction "COM_A1") (pintype "passive"))
    )
    (net (code "42") (name "Net-(U20-DIR)") (class "Default")
      (node (ref "R27") (pin "2") (pinfunction "2_2") (pintype "passive"))
      (node (ref "U20") (pin "B2") (pinfunction "DIR_B2") (pintype "passive"))
      (node (ref "U34") (pin "14") (pinfunction "IO1.4_14") (pintype "passive"))
    )
    (net (code "43") (name "Net-(U21-DIR)") (class "Default")
      (node (ref "R26") (pin "2") (pinfunction "2_2") (pintype "passive"))
      (node (ref "U21") (pin "B2") (pinfunction "DIR_B2") (pintype "passive"))
      (node (ref "U34") (pin "6") (pinfunction "IO0.5_6") (pintype "passive"))
    )
    (net (code "44") (name "Net-(U22-A)") (class "Default")
      (node (ref "R109") (pin "2") (pinfunction "2_2") (pintype "passive"))
      (node (ref "U22") (pin "D2") (pinfunction "A_D2") (pintype "passive"))
      (node (ref "U34") (pin "16") (pinfunction "IO1.6_16") (pintype "passive"))
    )
    (net (code "45") (name "Net-(U22-COM)") (class "Default")
      (node (ref "U22") (pin "A1") (pinfunction "COM_A1") (pintype "passive"))
      (node (ref "U23") (pin "C1") (pinfunction "A_C1") (pintype "passive"))
    )
    (net (code "46") (name "Net-(U22-Y2)") (class "Default")
      (node (ref "U22") (pin "C2") (pinfunction "Y2_C2") (pintype "passive"))
      (node (ref "U41") (pin "A1") (pinfunction "COM_A1") (pintype "passive"))
    )
    (net (code "47") (name "Net-(U23-DIR)") (class "Default")
      (node (ref "R29") (pin "2") (pinfunction "2_2") (pintype "passive"))
      (node (ref "U23") (pin "B2") (pinfunction "DIR_B2") (pintype "passive"))
      (node (ref "U34") (pin "13") (pinfunction "IO1.3_13") (pintype "passive"))
    )
    (net (code "48") (name "Net-(U24-DIR)") (class "Default")
      (node (ref "R24") (pin "2") (pinfunction "2_2") (pintype "passive"))
      (node (ref "U24") (pin "B2") (pinfunction "DIR_B2") (pintype "passive"))
      (node (ref "U34") (pin "5") (pinfunction "IO0.4_5") (pintype "passive"))
    )
    (net (code "49") (name "Net-(U25-A)") (class "Default")
      (node (ref "R110") (pin "2") (pinfunction "2_2") (pintype "passive"))
      (node (ref "U25") (pin "D2") (pinfunction "A_D2") (pintype "passive"))
      (node (ref "U34") (pin "17") (pinfunction "IO1.7_17") (pintype "passive"))
    )
    (net (code "50") (name "Net-(U25-COM)") (class "Default")
      (node (ref "U25") (pin "A1") (pinfunction "COM_A1") (pintype "passive"))
      (node (ref "U26") (pin "C1") (pinfunction "A_C1") (pintype "passive"))
    )
    (net (code "51") (name "Net-(U25-Y2)") (class "Default")
      (node (ref "U25") (pin "C2") (pinfunction "Y2_C2") (pintype "passive"))
      (node (ref "U40") (pin "A1") (pinfunction "COM_A1") (pintype "passive"))
    )
    (net (code "52") (name "Net-(U26-DIR)") (class "Default")
      (node (ref "R30") (pin "2") (pinfunction "2_2") (pintype "passive"))
      (node (ref "U26") (pin "B2") (pinfunction "DIR_B2") (pintype "passive"))
      (node (ref "U34") (pin "12") (pinfunction "IO1.2_12") (pintype "passive"))
    )
    (net (code "53") (name "Net-(U27-DIR)") (class "Default")
      (node (ref "R23") (pin "2") (pinfunction "2_2") (pintype "passive"))
      (node (ref "U27") (pin "B2") (pinfunction "DIR_B2") (pintype "passive"))
      (node (ref "U34") (pin "4") (pinfunction "IO0.3_4") (pintype "passive"))
    )
    (net (code "54") (name "Net-(U28-DIR)") (class "Default")
      (node (ref "R31") (pin "2") (pinfunction "2_2") (pintype "passive"))
      (node (ref "U28") (pin "B2") (pinfunction "DIR_B2") (pintype "passive"))
      (node (ref "U34") (pin "11") (pinfunction "IO1.1_11") (pintype "passive"))
    )
    (net (code "55") (name "Net-(U29-DIR)") (class "Default")
      (node (ref "R22") (pin "2") (pinfunction "2_2") (pintype "passive"))
      (node (ref "U29") (pin "B2") (pinfunction "DIR_B2") (pintype "passive"))
      (node (ref "U34") (pin "3") (pinfunction "IO0.2_3") (pintype "passive"))
    )
    (net (code "56") (name "Net-(U30-DIR)") (class "Default")
      (node (ref "R32") (pin "2") (pinfunction "2_2") (pintype "passive"))
      (node (ref "U30") (pin "B2") (pinfunction "DIR_B2") (pintype "passive"))
      (node (ref "U34") (pin "10") (pinfunction "IO1.0_10") (pintype "passive"))
    )
    (net (code "57") (name "Net-(U31-DIR)") (class "Default")
      (node (ref "R21") (pin "2") (pinfunction "2_2") (pintype "passive"))
      (node (ref "U31") (pin "B2") (pinfunction "DIR_B2") (pintype "passive"))
      (node (ref "U34") (pin "2") (pinfunction "IO0.1_2") (pintype "passive"))
    )
    (net (code "58") (name "Net-(U32-DIR)") (class "Default")
      (node (ref "R33") (pin "2") (pinfunction "2_2") (pintype "passive"))
      (node (ref "U32") (pin "B2") (pinfunction "DIR_B2") (pintype "passive"))
      (node (ref "U34") (pin "8") (pinfunction "IO0.7_8") (pintype "passive"))
    )
    (net (code "59") (name "Net-(U33-DIR)") (class "Default")
      (node (ref "R20") (pin "2") (pinfunction "2_2") (pintype "passive"))
      (node (ref "U33") (pin "B2") (pinfunction "DIR_B2") (pintype "passive"))
      (node (ref "U34") (pin "1") (pinfunction "IO0.0_1") (pintype "passive"))
    )
    (net (code "60") (name "Net-(U42-Y2)") (class "Default")
      (node (ref "U42") (pin "C2") (pinfunction "Y2_C2") (pintype "passive"))
      (node (ref "U44") (pin "2") (pinfunction "A_2") (pintype "passive"))
    )
    (net (code "61") (name "PWM0_OUT") (class "Default")
      (node (ref "R91") (pin "1") (pinfunction "1_1") (pintype "passive"))
      (node (ref "U27") (pin "C1") (pinfunction "A_C1") (pintype "passive"))
    )
    (net (code "62") (name "PWM1_OUT") (class "Default")
      (node (ref "R90") (pin "1") (pinfunction "1_1") (pintype "passive"))
      (node (ref "U21") (pin "C1") (pinfunction "A_C1") (pintype "passive"))
    )
    (net (code "63") (name "PWM2_OUT") (class "Default")
      (node (ref "R89") (pin "1") (pinfunction "1_1") (pintype "passive"))
      (node (ref "U19") (pin "C1") (pinfunction "A_C1") (pintype "passive"))
    )
    (net (code "64") (name "PWM3_OUT") (class "Default")
      (node (ref "R92") (pin "1") (pinfunction "1_1") (pintype "passive"))
      (node (ref "U28") (pin "C1") (pinfunction "A_C1") (pintype "passive"))
    )
    (net (code "65") (name "PWM4_OUT") (class "Default")
      (node (ref "R94") (pin "1") (pinfunction "1_1") (pintype "passive"))
      (node (ref "U25") (pin "B2") (pinfunction "Y1_B2") (pintype "passive"))
    )
    (net (code "66") (name "PWM5_OUT") (class "Default")
      (node (ref "R93") (pin "1") (pinfunction "1_1") (pintype "passive"))
      (node (ref "U22") (pin "B2") (pinfunction "Y1_B2") (pintype "passive"))
    )
    (net (code "67") (name "SHLD_RESET") (class "Default")
      (node (ref "C34") (pin "1") (pinfunction "1_1") (pintype "passive"))
      (node (ref "J4") (pin "5") (pinfunction "IO_5_5") (pintype "passive"))
      (node (ref "R19") (pin "1") (pinfunction "1_1") (pintype "passive"))
      (node (ref "SW1UI1") (pin "1") (pinfunction "A_1") (pintype "bidirectional"))
    )
    (net (code "68") (name "SPI_CLK_SEL") (class "Default")
      (node (ref "U43") (pin "D2") (pinfunction "A_D2") (pintype "passive"))
    )
    (net (code "69") (name "SPI_FS_SEL") (class "Default")
      (node (ref "U40") (pin "D2") (pinfunction "A_D2") (pintype "passive"))
    )
    (net (code "70") (name "SPI_RXD_SEL") (class "Default")
      (node (ref "U42") (pin "D2") (pinfunction "A_D2") (pintype "passive"))
    )
    (net (code "71") (name "SPI_TXD_SEL") (class "Default")
      (node (ref "U41") (pin "D2") (pinfunction "A_D2") (pintype "passive"))
    )
    (net (code "72") (name "V_1P80") (class "Default")
      (node (ref "R87") (pin "2") (pinfunction "2_2") (pintype "passive"))
      (node (ref "R89") (pin "2") (pinfunction "2_2") (pintype "passive"))
      (node (ref "R90") (pin "2") (pinfunction "2_2") (pintype "passive"))
      (node (ref "R91") (pin "2") (pinfunction "2_2") (pintype "passive"))
      (node (ref "R92") (pin "2") (pinfunction "2_2") (pintype "passive"))
      (node (ref "R93") (pin "2") (pinfunction "2_2") (pintype "passive"))
      (node (ref "R94") (pin "2") (pinfunction "2_2") (pintype "passive"))
      (node (ref "U18") (pin "A1") (pinfunction "VCCA_A1") (pintype "passive"))
      (node (ref "U19") (pin "A1") (pinfunction "VCCA_A1") (pintype "passive"))
      (node (ref "U20") (pin "A1") (pinfunction "VCCA_A1") (pintype "passive"))
      (node (ref "U21") (pin "A1") (pinfunction "VCCA_A1") (pintype "passive"))
      (node (ref "U22") (pin "A2") (pinfunction "VCC_A2") (pintype "passive"))
      (node (ref "U23") (pin "A1") (pinfunction "VCCA_A1") (pintype "passive"))
      (node (ref "U24") (pin "A1") (pinfunction "VCCA_A1") (pintype "passive"))
      (node (ref "U25") (pin "A2") (pinfunction "VCC_A2") (pintype "passive"))
      (node (ref "U26") (pin "A1") (pinfunction "VCCA_A1") (pintype "passive"))
      (node (ref "U27") (pin "A1") (pinfunction "VCCA_A1") (pintype "passive"))
      (node (ref "U28") (pin "A1") (pinfunction "VCCA_A1") (pintype "passive"))
      (node (ref "U29") (pin "A1") (pinfunction "VCCA_A1") (pintype "passive"))
      (node (ref "U30") (pin "A1") (pinfunction "VCCA_A1") (pintype "passive"))
      (node (ref "U31") (pin "A1") (pinfunction "VCCA_A1") (pintype "passive"))
      (node (ref "U32") (pin "A1") (pinfunction "VCCA_A1") (pintype "passive"))
      (node (ref "U33") (pin "A1") (pinfunction "VCCA_A1") (pintype "passive"))
      (node (ref "U40") (pin "A2") (pinfunction "VCC_A2") (pintype "passive"))
      (node (ref "U41") (pin "A2") (pinfunction "VCC_A2") (pintype "passive"))
      (node (ref "U42") (pin "A2") (pinfunction "VCC_A2") (pintype "passive"))
      (node (ref "U43") (pin "A2") (pinfunction "VCC_A2") (pintype "passive"))
      (node (ref "U44") (pin "6") (pinfunction "VCC_6") (pintype "passive"))
    )
    (net (code "73") (name "V_1P80_IO") (class "Default")
      (node (ref "U34") (pin "18") (pinfunction "A0_18") (pintype "passive"))
      (node (ref "U34") (pin "21") (pinfunction "VDD_21") (pintype "passive"))
      (node (ref "U34") (pin "23") (pinfunction "A1_23") (pintype "passive"))
    )
    (net (code "74") (name "V_SHIELD") (class "Default")
      (node (ref "R19") (pin "2") (pinfunction "2_2") (pintype "passive"))
    )
    (net (code "75") (name "V_SHIELD_SW") (class "Default")
      (node (ref "U18") (pin "A2") (pinfunction "VCCB_A2") (pintype "passive"))
      (node (ref "U19") (pin "A2") (pinfunction "VCCB_A2") (pintype "passive"))
      (node (ref "U20") (pin "A2") (pinfunction "VCCB_A2") (pintype "passive"))
      (node (ref "U21") (pin "A2") (pinfunction "VCCB_A2") (pintype "passive"))
      (node (ref "U23") (pin "A2") (pinfunction "VCCB_A2") (pintype "passive"))
      (node (ref "U24") (pin "A2") (pinfunction "VCCB_A2") (pintype "passive"))
      (node (ref "U26") (pin "A2") (pinfunction "VCCB_A2") (pintype "passive"))
      (node (ref "U27") (pin "A2") (pinfunction "VCCB_A2") (pintype "passive"))
      (node (ref "U28") (pin "A2") (pinfunction "VCCB_A2") (pintype "passive"))
      (node (ref "U29") (pin "A2") (pinfunction "VCCB_A2") (pintype "passive"))
      (node (ref "U30") (pin "A2") (pinfunction "VCCB_A2") (pintype "passive"))
      (node (ref "U31") (pin "A2") (pinfunction "VCCB_A2") (pintype "passive"))
      (node (ref "U32") (pin "A2") (pinfunction "VCCB_A2") (pintype "passive"))
      (node (ref "U33") (pin "A2") (pinfunction "VCCB_A2") (pintype "passive"))
    )
    (net (code "76") (name "V_SYS") (class "Default")
      (node (ref "R88") (pin "2") (pinfunction "2_2") (pintype "passive"))
    )
    (net (code "77") (name "unconnected-(U34-~{IN}T-Pad22)") (class "Default")
      (node (ref "U34") (pin "22") (pinfunction "~{IN}T_22") (pintype "passive"))
    )
    (net (code "78") (name "unconnected-(U44-NC-Pad5)") (class "Default")
      (node (ref "U44") (pin "5") (pinfunction "NC_5") (pintype "passive"))
    )
  )
)
